# RF_PLL_channel.net
KiCad netlist of a schematic drawn in Altium Designer
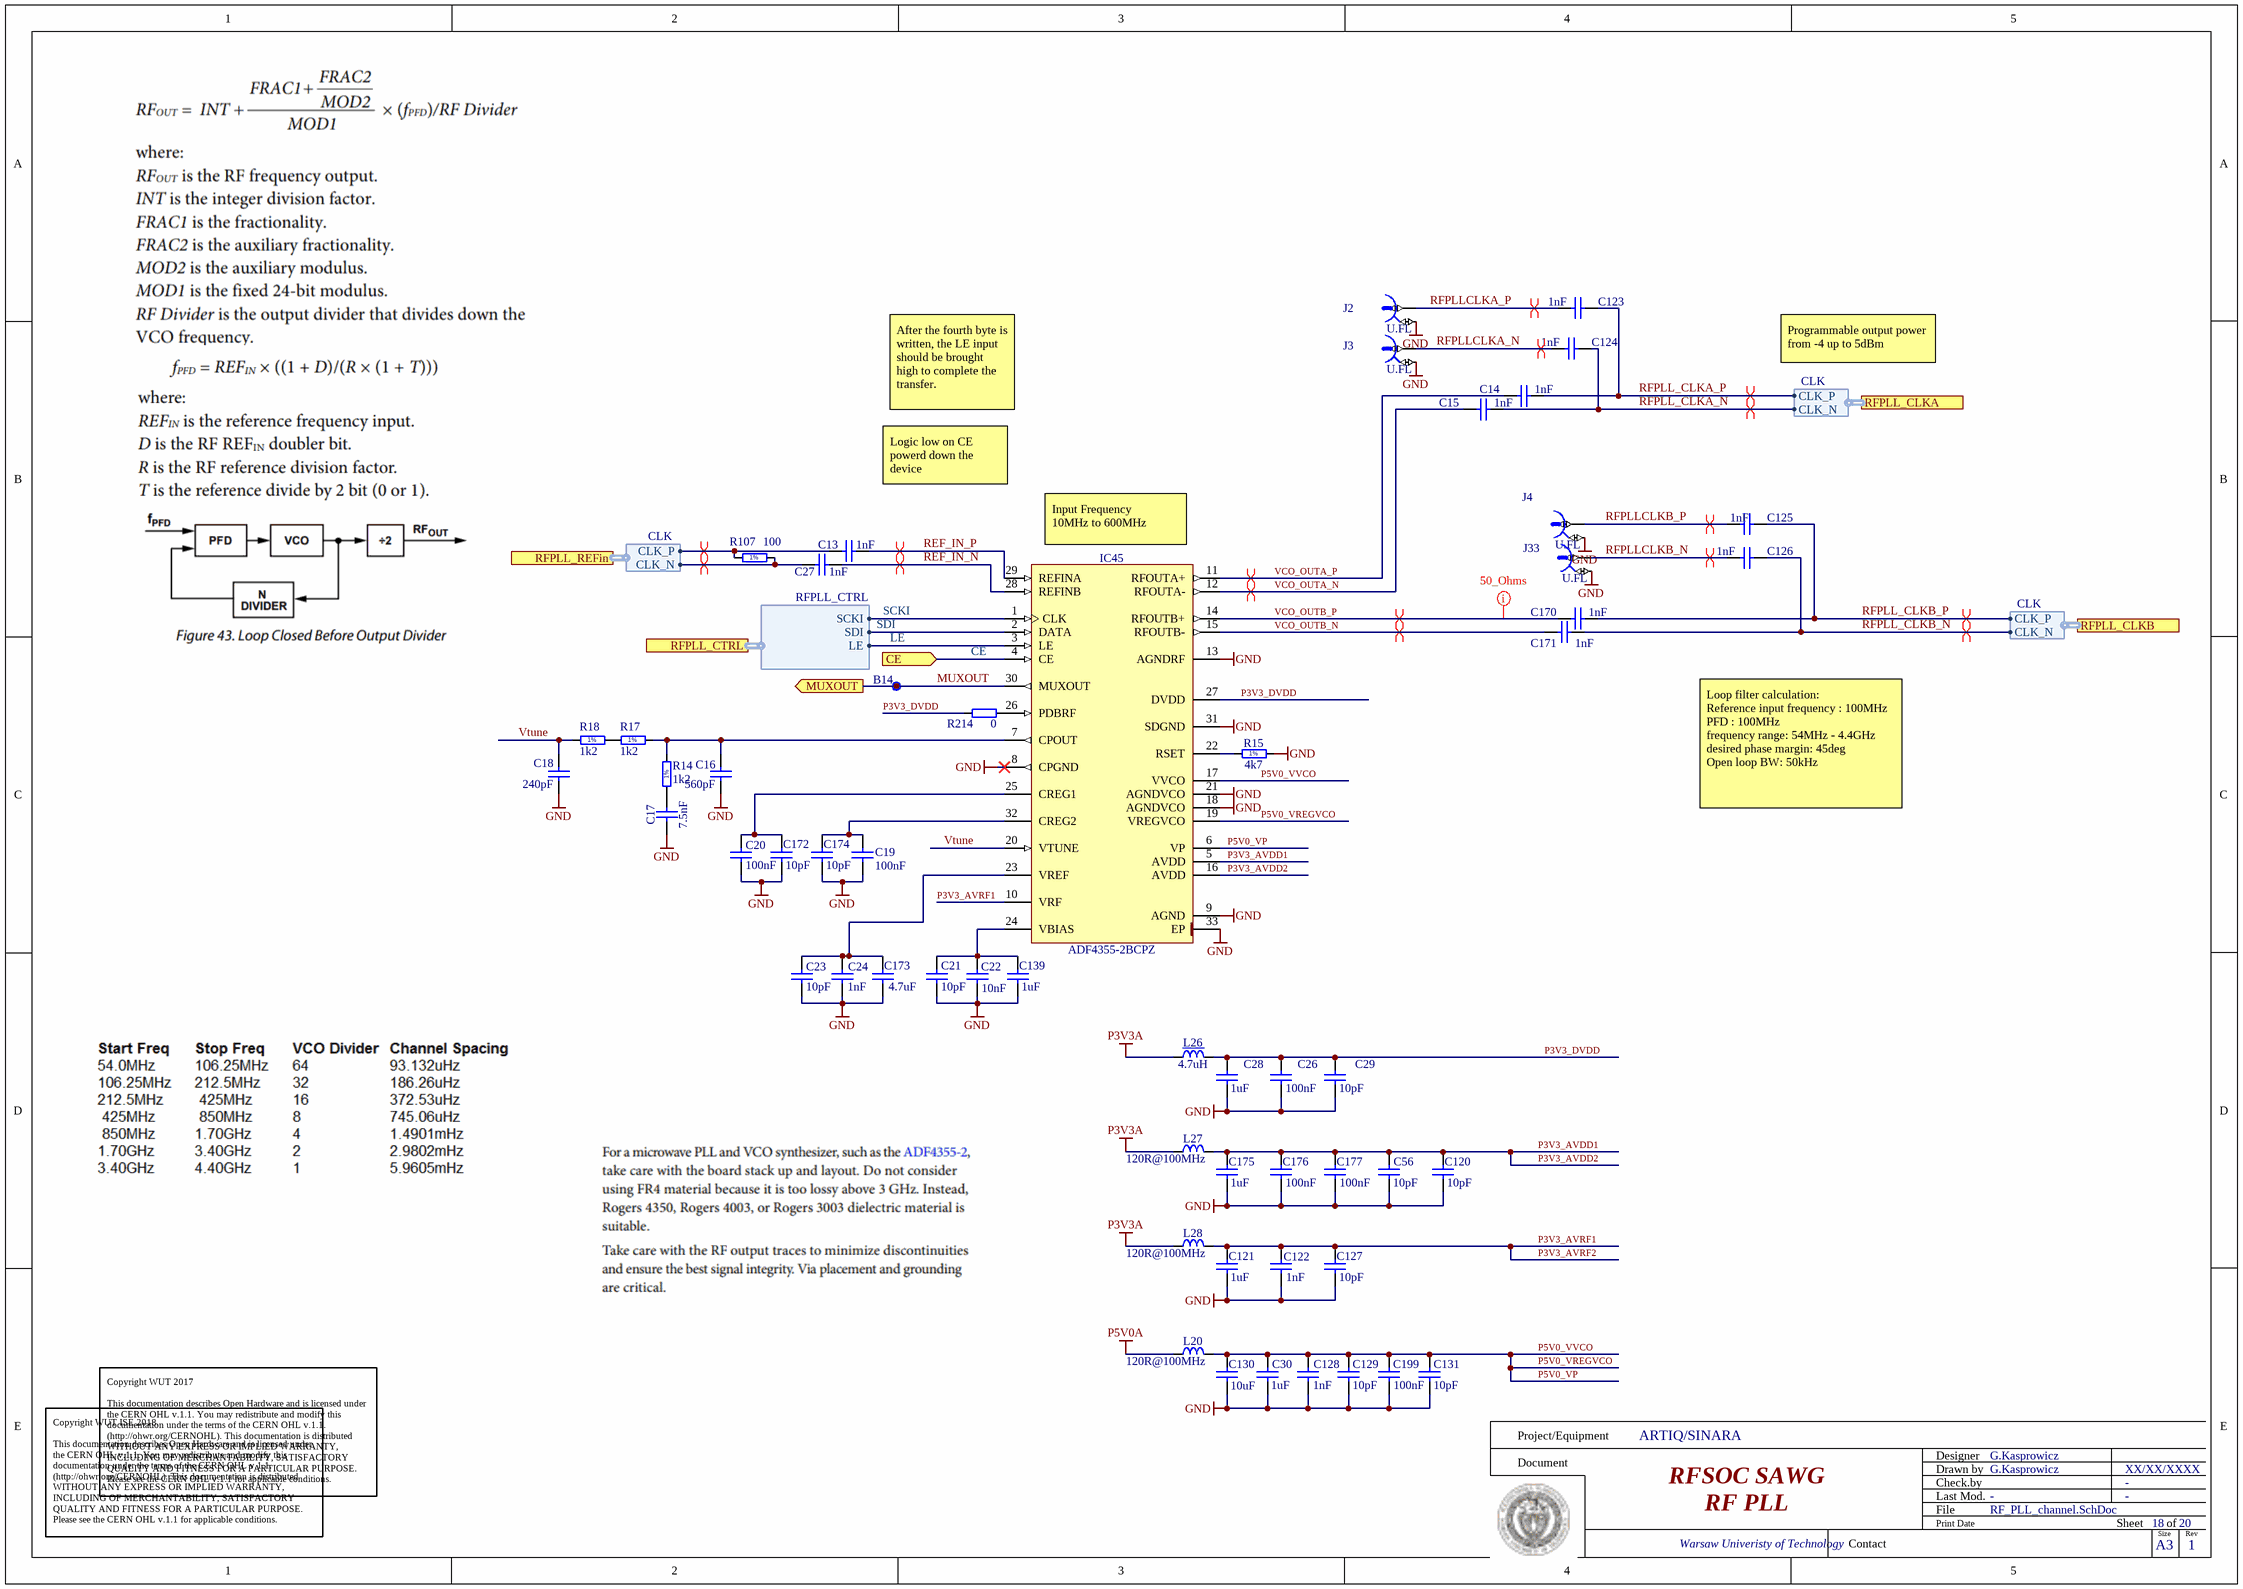
[diagram p0: RF_PLL_channel.SchDoc]

(export (version "E")
  (design (tool "Eeschema 10.0.6"))
  (components
    (comp (ref "B14")
      (value "SMD Pad")
      (footprint "C100")
      (description "Through Hole Pad")
      (fields (field (name "PART NUMBER") "SMD_PAD_D1MM") (field (name "AUTHOR") "CERN DEM JLC"))
      (libsource (lib "Eletro-mechanical") (part "Single SMD Pad (Round)"))
    )
    (comp (ref "C13")
      (value "1nF")
      (footprint "CAPC1005X55N")
      (description "Non-polarised capacitor")
      (fields
        (field (name "PART NUMBER") "CC0402_1NF_50V_10%_X7R")
        (field (name "VOLTAGE") "50V")
        (field (name "AUTHOR") "CERN DEM JLC")
      )
      (libsource (lib "Capacitors") (part "Capacitor - non polarized"))
    )
    (comp (ref "C14")
      (value "1nF")
      (footprint "CAPC1005X55N")
      (description "Non-polarised capacitor")
      (fields
        (field (name "PART NUMBER") "CC0402_1NF_50V_10%_X7R")
        (field (name "VOLTAGE") "50V")
        (field (name "AUTHOR") "CERN DEM JLC")
      )
      (libsource (lib "Capacitors") (part "Capacitor - non polarized"))
    )
    (comp (ref "C15")
      (value "1nF")
      (footprint "CAPC1005X55N")
      (description "Non-polarised capacitor")
      (fields
        (field (name "PART NUMBER") "CC0402_1NF_50V_10%_X7R")
        (field (name "VOLTAGE") "50V")
        (field (name "AUTHOR") "CERN DEM JLC")
      )
      (libsource (lib "Capacitors") (part "Capacitor - non polarized"))
    )
    (comp (ref "C16")
      (value "560pF")
      (footprint "CAPC1005X55N")
      (description "Non-polarised capacitor")
      (fields
        (field (name "PART NUMBER") "CC0402_560PF_50V_5%_C0G")
        (field (name "VOLTAGE") "50V")
        (field (name "AUTHOR") "CERN DEM JLC")
      )
      (libsource (lib "Capacitors") (part "Capacitor - non polarized"))
    )
    (comp (ref "C17")
      (value "7.5nF")
      (footprint "CAPC1608X87N")
      (description "Non-polarised capacitor")
      (fields
        (field (name "PART NUMBER") "CC0603_7.5NF_25V_5%_C0G")
        (field (name "VOLTAGE") "25V")
        (field (name "AUTHOR") "CERN DEM JLC")
      )
      (libsource (lib "Capacitors") (part "Capacitor - non polarized"))
    )
    (comp (ref "C18")
      (value "240pF")
      (footprint "CAPC1005X55N")
      (description "Non-polarised capacitor")
      (fields
        (field (name "PART NUMBER") "CC0402_240PF_50V_5%_C0G")
        (field (name "VOLTAGE") "50V")
        (field (name "AUTHOR") "CERN DEM JLC")
      )
      (libsource (lib "Capacitors") (part "Capacitor - non polarized"))
    )
    (comp (ref "C19")
      (value "100nF")
      (footprint "CAPC1005X55N")
      (description "Non-polarised capacitor")
      (fields
        (field (name "PART NUMBER") "CC0402_100NF_16V_10%_X5R")
        (field (name "VOLTAGE") "16V")
        (field (name "AUTHOR") "CERN DEM JLC")
      )
      (libsource (lib "Capacitors") (part "Capacitor - non polarized"))
    )
    (comp (ref "C20")
      (value "100nF")
      (footprint "CAPC1005X55N")
      (description "Non-polarised capacitor")
      (fields
        (field (name "PART NUMBER") "CC0402_100NF_16V_10%_X5R")
        (field (name "VOLTAGE") "16V")
        (field (name "AUTHOR") "CERN DEM JLC")
      )
      (libsource (lib "Capacitors") (part "Capacitor - non polarized"))
    )
    (comp (ref "C21")
      (value "10pF")
      (footprint "CAPC1005X55N")
      (description "Non-polarised capacitor")
      (fields
        (field (name "PART NUMBER") "CC0402_10PF_50V_5%_C0G")
        (field (name "VOLTAGE") "50V")
        (field (name "AUTHOR") "CERN DEM JLC")
      )
      (libsource (lib "Capacitors") (part "Capacitor - non polarized"))
    )
    (comp (ref "C22")
      (value "10nF")
      (footprint "CAPC1005X55N")
      (description "Non-polarised capacitor")
      (fields
        (field (name "PART NUMBER") "CC0402_10NF_16V_10%_X7R")
        (field (name "VOLTAGE") "16V")
        (field (name "AUTHOR") "CERN DEM JLC")
      )
      (libsource (lib "Capacitors") (part "Capacitor - non polarized"))
    )
    (comp (ref "C23")
      (value "10pF")
      (footprint "CAPC1005X55N")
      (description "Non-polarised capacitor")
      (fields
        (field (name "PART NUMBER") "CC0402_10PF_50V_5%_C0G")
        (field (name "VOLTAGE") "50V")
        (field (name "AUTHOR") "CERN DEM JLC")
      )
      (libsource (lib "Capacitors") (part "Capacitor - non polarized"))
    )
    (comp (ref "C24")
      (value "1nF")
      (footprint "CAPC1005X55N")
      (description "Non-polarised capacitor")
      (fields
        (field (name "PART NUMBER") "CC0402_1NF_50V_10%_X7R")
        (field (name "VOLTAGE") "50V")
        (field (name "AUTHOR") "CERN DEM JLC")
      )
      (libsource (lib "Capacitors") (part "Capacitor - non polarized"))
    )
    (comp (ref "C26")
      (value "100nF")
      (footprint "CAPC1005X55N")
      (description "Non-polarised capacitor")
      (fields
        (field (name "PART NUMBER") "CC0402_100NF_16V_10%_X5R")
        (field (name "VOLTAGE") "16V")
        (field (name "AUTHOR") "CERN DEM JLC")
      )
      (libsource (lib "Capacitors") (part "Capacitor - non polarized"))
    )
    (comp (ref "C27")
      (value "1nF")
      (footprint "CAPC1005X55N")
      (description "Non-polarised capacitor")
      (fields
        (field (name "PART NUMBER") "CC0402_1NF_50V_10%_X7R")
        (field (name "VOLTAGE") "50V")
        (field (name "AUTHOR") "CERN DEM JLC")
      )
      (libsource (lib "Capacitors") (part "Capacitor - non polarized"))
    )
    (comp (ref "C28")
      (value "1uF")
      (footprint "CAPC1005X55N")
      (description "Non-polarised capacitor")
      (fields
        (field (name "PART NUMBER") "CC0402_1UF_16V_10%_X5R")
        (field (name "VOLTAGE") "16V")
        (field (name "AUTHOR") "CERN DEM JLC")
      )
      (libsource (lib "Capacitors") (part "Capacitor - non polarized"))
    )
    (comp (ref "C29")
      (value "10pF")
      (footprint "CAPC1005X55N")
      (description "Non-polarised capacitor")
      (fields
        (field (name "PART NUMBER") "CC0402_10PF_50V_5%_C0G")
        (field (name "VOLTAGE") "50V")
        (field (name "AUTHOR") "CERN DEM JLC")
      )
      (libsource (lib "Capacitors") (part "Capacitor - non polarized"))
    )
    (comp (ref "C30")
      (value "1uF")
      (footprint "CAPC1005X55N")
      (description "Non-polarised capacitor")
      (fields
        (field (name "PART NUMBER") "CC0402_1UF_16V_10%_X5R")
        (field (name "VOLTAGE") "16V")
        (field (name "AUTHOR") "CERN DEM JLC")
      )
      (libsource (lib "Capacitors") (part "Capacitor - non polarized"))
    )
    (comp (ref "C56")
      (value "10pF")
      (footprint "CAPC1005X55N")
      (description "Non-polarised capacitor")
      (fields
        (field (name "PART NUMBER") "CC0402_10PF_50V_5%_C0G")
        (field (name "VOLTAGE") "50V")
        (field (name "AUTHOR") "CERN DEM JLC")
      )
      (libsource (lib "Capacitors") (part "Capacitor - non polarized"))
    )
    (comp (ref "C120")
      (value "10pF")
      (footprint "CAPC1005X55N")
      (description "Non-polarised capacitor")
      (fields
        (field (name "PART NUMBER") "CC0402_10PF_50V_5%_C0G")
        (field (name "VOLTAGE") "50V")
        (field (name "AUTHOR") "CERN DEM JLC")
      )
      (libsource (lib "Capacitors") (part "Capacitor - non polarized"))
    )
    (comp (ref "C121")
      (value "1uF")
      (footprint "CAPC1005X55N")
      (description "Non-polarised capacitor")
      (fields
        (field (name "PART NUMBER") "CC0402_1UF_16V_10%_X5R")
        (field (name "VOLTAGE") "16V")
        (field (name "AUTHOR") "CERN DEM JLC")
      )
      (libsource (lib "Capacitors") (part "Capacitor - non polarized"))
    )
    (comp (ref "C122")
      (value "1nF")
      (footprint "CAPC1005X55N")
      (description "Non-polarised capacitor")
      (fields
        (field (name "PART NUMBER") "CC0402_1NF_50V_10%_X7R")
        (field (name "VOLTAGE") "50V")
        (field (name "AUTHOR") "CERN DEM JLC")
      )
      (libsource (lib "Capacitors") (part "Capacitor - non polarized"))
    )
    (comp (ref "C123")
      (value "1nF")
      (footprint "CAPC1005X55N")
      (description "Non-polarised capacitor")
      (fields
        (field (name "PART NUMBER") "CC0402_1NF_50V_10%_X7R")
        (field (name "VOLTAGE") "50V")
        (field (name "AUTHOR") "CERN DEM JLC")
      )
      (libsource (lib "Capacitors") (part "Capacitor - non polarized"))
    )
    (comp (ref "C124")
      (value "1nF")
      (footprint "CAPC1005X55N")
      (description "Non-polarised capacitor")
      (fields
        (field (name "PART NUMBER") "CC0402_1NF_50V_10%_X7R")
        (field (name "VOLTAGE") "50V")
        (field (name "AUTHOR") "CERN DEM JLC")
      )
      (libsource (lib "Capacitors") (part "Capacitor - non polarized"))
    )
    (comp (ref "C125")
      (value "1nF")
      (footprint "CAPC1005X55N")
      (description "Non-polarised capacitor")
      (fields
        (field (name "PART NUMBER") "CC0402_1NF_50V_10%_X7R")
        (field (name "VOLTAGE") "50V")
        (field (name "AUTHOR") "CERN DEM JLC")
      )
      (libsource (lib "Capacitors") (part "Capacitor - non polarized"))
    )
    (comp (ref "C126")
      (value "1nF")
      (footprint "CAPC1005X55N")
      (description "Non-polarised capacitor")
      (fields
        (field (name "PART NUMBER") "CC0402_1NF_50V_10%_X7R")
        (field (name "VOLTAGE") "50V")
        (field (name "AUTHOR") "CERN DEM JLC")
      )
      (libsource (lib "Capacitors") (part "Capacitor - non polarized"))
    )
    (comp (ref "C127")
      (value "10pF")
      (footprint "CAPC1005X55N")
      (description "Non-polarised capacitor")
      (fields
        (field (name "PART NUMBER") "CC0402_10PF_50V_5%_C0G")
        (field (name "VOLTAGE") "50V")
        (field (name "AUTHOR") "CERN DEM JLC")
      )
      (libsource (lib "Capacitors") (part "Capacitor - non polarized"))
    )
    (comp (ref "C128")
      (value "1nF")
      (footprint "CAPC1005X55N")
      (description "Non-polarised capacitor")
      (fields
        (field (name "PART NUMBER") "CC0402_1NF_50V_10%_X7R")
        (field (name "VOLTAGE") "50V")
        (field (name "AUTHOR") "CERN DEM JLC")
      )
      (libsource (lib "Capacitors") (part "Capacitor - non polarized"))
    )
    (comp (ref "C129")
      (value "10pF")
      (footprint "CAPC1005X55N")
      (description "Non-polarised capacitor")
      (fields
        (field (name "PART NUMBER") "CC0402_10PF_50V_5%_C0G")
        (field (name "VOLTAGE") "50V")
        (field (name "AUTHOR") "CERN DEM JLC")
      )
      (libsource (lib "Capacitors") (part "Capacitor - non polarized"))
    )
    (comp (ref "C130")
      (value "10uF")
      (footprint "CAPC1608X80N")
      (description "Non-polarised capacitor")
      (fields
        (field (name "PART NUMBER") "CC0603_10UF_16V_20%_X5R")
        (field (name "VOLTAGE") "16V")
        (field (name "AUTHOR") "CERN DEM MR")
      )
      (libsource (lib "Capacitors") (part "Capacitor - non polarized"))
    )
    (comp (ref "C131")
      (value "10pF")
      (footprint "CAPC1005X55N")
      (description "Non-polarised capacitor")
      (fields
        (field (name "PART NUMBER") "CC0402_10PF_50V_5%_C0G")
        (field (name "VOLTAGE") "50V")
        (field (name "AUTHOR") "CERN DEM JLC")
      )
      (libsource (lib "Capacitors") (part "Capacitor - non polarized"))
    )
    (comp (ref "C139")
      (value "1uF")
      (footprint "CAPC1005X55N")
      (description "Non-polarised capacitor")
      (fields
        (field (name "PART NUMBER") "CC0402_1UF_16V_10%_X5R")
        (field (name "VOLTAGE") "16V")
        (field (name "AUTHOR") "CERN DEM JLC")
      )
      (libsource (lib "Capacitors") (part "Capacitor - non polarized"))
    )
    (comp (ref "C170")
      (value "1nF")
      (footprint "CAPC1005X55N")
      (description "Non-polarised capacitor")
      (fields
        (field (name "PART NUMBER") "CC0402_1NF_50V_10%_X7R")
        (field (name "VOLTAGE") "50V")
        (field (name "AUTHOR") "CERN DEM JLC")
      )
      (libsource (lib "Capacitors") (part "Capacitor - non polarized"))
    )
    (comp (ref "C171")
      (value "1nF")
      (footprint "CAPC1005X55N")
      (description "Non-polarised capacitor")
      (fields
        (field (name "PART NUMBER") "CC0402_1NF_50V_10%_X7R")
        (field (name "VOLTAGE") "50V")
        (field (name "AUTHOR") "CERN DEM JLC")
      )
      (libsource (lib "Capacitors") (part "Capacitor - non polarized"))
    )
    (comp (ref "C172")
      (value "10pF")
      (footprint "CAPC1005X55N")
      (description "Non-polarised capacitor")
      (fields
        (field (name "PART NUMBER") "CC0402_10PF_50V_5%_C0G")
        (field (name "VOLTAGE") "50V")
        (field (name "AUTHOR") "CERN DEM JLC")
      )
      (libsource (lib "Capacitors") (part "Capacitor - non polarized"))
    )
    (comp (ref "C173")
      (value "4.7uF")
      (footprint "CAPC1608X80N")
      (description "Non-polarised capacitor")
      (fields
        (field (name "PART NUMBER") "CC0603_4U7F_16V_10%_X5R")
        (field (name "VOLTAGE") "16V")
        (field (name "AUTHOR") "CERN DEM MR")
      )
      (libsource (lib "Capacitors") (part "Capacitor - non polarized"))
    )
    (comp (ref "C174")
      (value "10pF")
      (footprint "CAPC1005X55N")
      (description "Non-polarised capacitor")
      (fields
        (field (name "PART NUMBER") "CC0402_10PF_50V_5%_C0G")
        (field (name "VOLTAGE") "50V")
        (field (name "AUTHOR") "CERN DEM JLC")
      )
      (libsource (lib "Capacitors") (part "Capacitor - non polarized"))
    )
    (comp (ref "C175")
      (value "1uF")
      (footprint "CAPC1005X55N")
      (description "Non-polarised capacitor")
      (fields
        (field (name "PART NUMBER") "CC0402_1UF_16V_10%_X5R")
        (field (name "VOLTAGE") "16V")
        (field (name "AUTHOR") "CERN DEM JLC")
      )
      (libsource (lib "Capacitors") (part "Capacitor - non polarized"))
    )
    (comp (ref "C176")
      (value "100nF")
      (footprint "CAPC1005X55N")
      (description "Non-polarised capacitor")
      (fields
        (field (name "PART NUMBER") "CC0402_100NF_16V_10%_X5R")
        (field (name "VOLTAGE") "16V")
        (field (name "AUTHOR") "CERN DEM JLC")
      )
      (libsource (lib "Capacitors") (part "Capacitor - non polarized"))
    )
    (comp (ref "C177")
      (value "100nF")
      (footprint "CAPC1005X55N")
      (description "Non-polarised capacitor")
      (fields
        (field (name "PART NUMBER") "CC0402_100NF_16V_10%_X5R")
        (field (name "VOLTAGE") "16V")
        (field (name "AUTHOR") "CERN DEM JLC")
      )
      (libsource (lib "Capacitors") (part "Capacitor - non polarized"))
    )
    (comp (ref "C199")
      (value "100nF")
      (footprint "CAPC1005X55N")
      (description "Non-polarised capacitor")
      (fields
        (field (name "PART NUMBER") "CC0402_100NF_16V_10%_X5R")
        (field (name "VOLTAGE") "16V")
        (field (name "AUTHOR") "CERN DEM JLC")
      )
      (libsource (lib "Capacitors") (part "Capacitor - non polarized"))
    )
    (comp (ref "IC45")
      (value "ADF4355-2BCPZ")
      (footprint "QFN50P500X500X80-33N-S375")
      (description "Microwave Wideband Synthesizer with Integrated VCO")
      (fields
        (field (name "MANUFACTURER") "ANALOG DEVICES")
        (field (name "MANUFACTURER PART NUMBER") "ADF4355-2BCP")
        (field (name "AUTHOR") "CERN DEM BC")
      )
      (libsource (lib "ICs And Semiconductors") (part "ADF4355-2"))
    )
    (comp (ref "J2")
      (value "U.FL")
      (footprint "HIROSE_U.FL-R-SMT-1(10)")
      (fields
        (field (name "PART NUMBER") "HIROSE_U.FL-R-SMT-1(10)")
        (field (name "MANUFACTURER") "HIROSE (HRS)")
        (field (name "MANUFACTURER PART NUMBER") "U.FL-R-SMT-1(10)")
        (field (name "AUTHOR") "CERN DEM JLC")
      )
      (libsource (lib "Connectors") (part "Coax_1Male_1Shield"))
    )
    (comp (ref "J3")
      (value "U.FL")
      (footprint "HIROSE_U.FL-R-SMT-1(10)")
      (fields
        (field (name "PART NUMBER") "HIROSE_U.FL-R-SMT-1(10)")
        (field (name "MANUFACTURER") "HIROSE (HRS)")
        (field (name "MANUFACTURER PART NUMBER") "U.FL-R-SMT-1(10)")
        (field (name "AUTHOR") "CERN DEM JLC")
      )
      (libsource (lib "Connectors") (part "Coax_1Male_1Shield"))
    )
    (comp (ref "J4")
      (value "U.FL")
      (footprint "HIROSE_U.FL-R-SMT-1(10)")
      (fields
        (field (name "PART NUMBER") "HIROSE_U.FL-R-SMT-1(10)")
        (field (name "MANUFACTURER") "HIROSE (HRS)")
        (field (name "MANUFACTURER PART NUMBER") "U.FL-R-SMT-1(10)")
        (field (name "AUTHOR") "CERN DEM JLC")
      )
      (libsource (lib "Connectors") (part "Coax_1Male_1Shield"))
    )
    (comp (ref "J33")
      (value "U.FL")
      (footprint "HIROSE_U.FL-R-SMT-1(10)")
      (fields
        (field (name "PART NUMBER") "HIROSE_U.FL-R-SMT-1(10)")
        (field (name "MANUFACTURER") "HIROSE (HRS)")
        (field (name "MANUFACTURER PART NUMBER") "U.FL-R-SMT-1(10)")
        (field (name "AUTHOR") "CERN DEM JLC")
      )
      (libsource (lib "Connectors") (part "Coax_1Male_1Shield"))
    )
    (comp (ref "L20")
      (value "120R@100MHz")
      (footprint "INDC1608X95N")
      (description "Inductor")
      (fields
        (field (name "PART NUMBER") "IND0603_MURATA_BLM18PG121SN1D")
        (field (name "POWER") "2A")
        (field (name "AUTHOR") "CERN DEM BC")
      )
      (libsource (lib "Inductors & Transformers") (part "Inductor"))
    )
    (comp (ref "L26")
      (value "4.7uH")
      (footprint "INDC2012X145N")
      (description "Inductor With Core")
      (fields
        (field (name "PART NUMBER") "IND0805_4.7UH_20%_KEMET_L-DWI")
        (field (name "POWER") "360mA")
        (field (name "AUTHOR") "CERN DEM JLC")
      )
      (libsource (lib "Inductors & Transformers") (part "Inductor With Magnetic core"))
    )
    (comp (ref "L27")
      (value "120R@100MHz")
      (footprint "INDC1608X95N")
      (description "Inductor")
      (fields
        (field (name "PART NUMBER") "IND0603_MURATA_BLM18PG121SN1D")
        (field (name "POWER") "2A")
        (field (name "AUTHOR") "CERN DEM BC")
      )
      (libsource (lib "Inductors & Transformers") (part "Inductor"))
    )
    (comp (ref "L28")
      (value "120R@100MHz")
      (footprint "INDC1608X95N")
      (description "Inductor")
      (fields
        (field (name "PART NUMBER") "IND0603_MURATA_BLM18PG121SN1D")
        (field (name "POWER") "2A")
        (field (name "AUTHOR") "CERN DEM BC")
      )
      (libsource (lib "Inductors & Transformers") (part "Inductor"))
    )
    (comp (ref "R14")
      (value "1k2")
      (footprint "RESC1005X40N")
      (description "Resistor - 1%")
      (fields
        (field (name "PART NUMBER") "R0402_1K2_1%_0.0625W_100PPM")
        (field (name "POWER") "0.0625W")
        (field (name "AUTHOR") "CERN DEM JLC")
      )
      (libsource (lib "Resistors") (part "Resistor - 1%"))
    )
    (comp (ref "R15")
      (value "4k7")
      (footprint "RESC1005X40N")
      (description "Resistor - 1%")
      (fields
        (field (name "PART NUMBER") "R0402_4K7_1%_0.0625W_100PPM")
        (field (name "POWER") "0.0625W")
        (field (name "AUTHOR") "CERN DEM JLC")
      )
      (libsource (lib "Resistors") (part "Resistor - 1%"))
    )
    (comp (ref "R17")
      (value "1k2")
      (footprint "RESC1005X40N")
      (description "Resistor - 1%")
      (fields
        (field (name "PART NUMBER") "R0402_1K2_1%_0.0625W_100PPM")
        (field (name "POWER") "0.0625W")
        (field (name "AUTHOR") "CERN DEM JLC")
      )
      (libsource (lib "Resistors") (part "Resistor - 1%"))
    )
    (comp (ref "R18")
      (value "1k2")
      (footprint "RESC1005X40N")
      (description "Resistor - 1%")
      (fields
        (field (name "PART NUMBER") "R0402_1K2_1%_0.0625W_100PPM")
        (field (name "POWER") "0.0625W")
        (field (name "AUTHOR") "CERN DEM JLC")
      )
      (libsource (lib "Resistors") (part "Resistor - 1%"))
    )
    (comp (ref "R107")
      (value "100")
      (footprint "RESC1005X40N")
      (description "Resistor - 1%")
      (fields
        (field (name "PART NUMBER") "R0402_100R_1%_0.0625W_100PPM")
        (field (name "POWER") "0.0625W")
        (field (name "AUTHOR") "CERN DEM JLC")
      )
      (libsource (lib "Resistors") (part "Resistor - 1%"))
    )
    (comp (ref "R214")
      (value "0")
      (footprint "RESC1005X40N")
      (description "Resistor")
      (fields
        (field (name "PART NUMBER") "R0402_0R_JUMPER")
        (field (name "MANUFACTURER") "GENERIC")
        (field (name "AUTHOR") "CERN DEM JLC")
      )
      (libsource (lib "Resistors") (part "Resistor"))
    )
  )
  (nets
    (net (code "3") (name "/CE") (class "Default")
      (node (ref "IC45") (pin "4") (pinfunction "CE_4") (pintype "input"))
    )
    (net (code "4") (name "/LE") (class "Default")
      (node (ref "IC45") (pin "3") (pinfunction "LE_3") (pintype "input"))
    )
    (net (code "5") (name "/MUXOUT") (class "Default")
      (node (ref "B14") (pin "1") (pinfunction "1_1") (pintype "bidirectional"))
      (node (ref "IC45") (pin "30") (pinfunction "MUXOUT_30") (pintype "output"))
    )
    (net (code "6") (name "/P3V3_AVDD1") (class "Default")
      (node (ref "C120") (pin "2") (pinfunction "2_2") (pintype "passive"))
      (node (ref "C175") (pin "2") (pinfunction "2_2") (pintype "passive"))
      (node (ref "C176") (pin "2") (pinfunction "2_2") (pintype "passive"))
      (node (ref "C177") (pin "2") (pinfunction "2_2") (pintype "passive"))
      (node (ref "C56") (pin "2") (pinfunction "2_2") (pintype "passive"))
      (node (ref "IC45") (pin "16") (pinfunction "AVDD_16") (pintype "power_in"))
      (node (ref "IC45") (pin "5") (pinfunction "AVDD_5") (pintype "power_in"))
      (node (ref "L27") (pin "1") (pinfunction "1_1") (pintype "passive"))
    )
    (net (code "7") (name "/P3V3_AVRF1") (class "Default")
      (node (ref "C121") (pin "2") (pinfunction "2_2") (pintype "passive"))
      (node (ref "C122") (pin "2") (pinfunction "2_2") (pintype "passive"))
      (node (ref "C127") (pin "2") (pinfunction "2_2") (pintype "passive"))
      (node (ref "IC45") (pin "10") (pinfunction "VRF_10") (pintype "passive"))
      (node (ref "L28") (pin "1") (pinfunction "1_1") (pintype "passive"))
    )
    (net (code "8") (name "/P3V3_DVDD") (class "Default")
      (node (ref "C26") (pin "2") (pinfunction "2_2") (pintype "passive"))
      (node (ref "C28") (pin "2") (pinfunction "2_2") (pintype "passive"))
      (node (ref "C29") (pin "2") (pinfunction "2_2") (pintype "passive"))
      (node (ref "IC45") (pin "27") (pinfunction "DVDD_27") (pintype "power_in"))
      (node (ref "L26") (pin "2") (pinfunction "2_2") (pintype "passive"))
      (node (ref "R214") (pin "1") (pinfunction "1_1") (pintype "passive"))
    )
    (net (code "9") (name "/P5V0_VP") (class "Default")
      (node (ref "C128") (pin "2") (pinfunction "2_2") (pintype "passive"))
      (node (ref "C129") (pin "2") (pinfunction "2_2") (pintype "passive"))
      (node (ref "C130") (pin "2") (pinfunction "2_2") (pintype "passive"))
      (node (ref "C131") (pin "2") (pinfunction "2_2") (pintype "passive"))
      (node (ref "C199") (pin "2") (pinfunction "2_2") (pintype "passive"))
      (node (ref "C30") (pin "2") (pinfunction "2_2") (pintype "passive"))
      (node (ref "IC45") (pin "17") (pinfunction "VVCO_17") (pintype "power_in"))
      (node (ref "IC45") (pin "19") (pinfunction "VREGVCO_19") (pintype "power_in"))
      (node (ref "IC45") (pin "6") (pinfunction "VP_6") (pintype "power_in"))
      (node (ref "L20") (pin "1") (pinfunction "1_1") (pintype "passive"))
    )
    (net (code "10") (name "/REF_IN_N") (class "Default")
      (node (ref "C27") (pin "2") (pinfunction "2_2") (pintype "passive"))
      (node (ref "IC45") (pin "28") (pinfunction "REFINB_28") (pintype "input"))
    )
    (net (code "11") (name "/REF_IN_P") (class "Default")
      (node (ref "C13") (pin "2") (pinfunction "2_2") (pintype "passive"))
      (node (ref "IC45") (pin "29") (pinfunction "REFINA_29") (pintype "input"))
    )
    (net (code "12") (name "/RFPLLCLKA_N") (class "Default")
      (node (ref "C124") (pin "2") (pinfunction "2_2") (pintype "passive"))
      (node (ref "J3") (pin "1") (pinfunction "1_1") (pintype "bidirectional"))
    )
    (net (code "13") (name "/RFPLLCLKA_P") (class "Default")
      (node (ref "C123") (pin "2") (pinfunction "2_2") (pintype "passive"))
      (node (ref "J2") (pin "1") (pinfunction "1_1") (pintype "bidirectional"))
    )
    (net (code "14") (name "/RFPLLCLKB_N") (class "Default")
      (node (ref "C126") (pin "2") (pinfunction "2_2") (pintype "passive"))
      (node (ref "J33") (pin "1") (pinfunction "1_1") (pintype "bidirectional"))
    )
    (net (code "15") (name "/RFPLLCLKB_P") (class "Default")
      (node (ref "C125") (pin "2") (pinfunction "2_2") (pintype "passive"))
      (node (ref "J4") (pin "1") (pinfunction "1_1") (pintype "bidirectional"))
    )
    (net (code "16") (name "/RFPLL_CLKA_N") (class "Default")
      (node (ref "C124") (pin "1") (pinfunction "1_1") (pintype "passive"))
      (node (ref "C15") (pin "2") (pinfunction "2_2") (pintype "passive"))
    )
    (net (code "17") (name "/RFPLL_CLKA_P") (class "Default")
      (node (ref "C123") (pin "1") (pinfunction "1_1") (pintype "passive"))
      (node (ref "C14") (pin "2") (pinfunction "2_2") (pintype "passive"))
    )
    (net (code "18") (name "/RFPLL_CLKB_N") (class "Default")
      (node (ref "C126") (pin "1") (pinfunction "1_1") (pintype "passive"))
      (node (ref "C171") (pin "2") (pinfunction "2_2") (pintype "passive"))
    )
    (net (code "19") (name "/RFPLL_CLKB_P") (class "Default")
      (node (ref "C125") (pin "1") (pinfunction "1_1") (pintype "passive"))
      (node (ref "C170") (pin "2") (pinfunction "2_2") (pintype "passive"))
    )
    (net (code "20") (name "/SCKI") (class "Default")
      (node (ref "IC45") (pin "1") (pinfunction "CLK_1") (pintype "input"))
    )
    (net (code "21") (name "/SDI") (class "Default")
      (node (ref "IC45") (pin "2") (pinfunction "DATA_2") (pintype "input"))
    )
    (net (code "22") (name "/VCO_OUTA_N") (class "Default")
      (node (ref "C15") (pin "1") (pinfunction "1_1") (pintype "passive"))
      (node (ref "IC45") (pin "12") (pinfunction "RFOUTA-_12") (pintype "output"))
    )
    (net (code "23") (name "/VCO_OUTA_P") (class "Default")
      (node (ref "C14") (pin "1") (pinfunction "1_1") (pintype "passive"))
      (node (ref "IC45") (pin "11") (pinfunction "RFOUTA+_11") (pintype "output"))
    )
    (net (code "24") (name "/VCO_OUTB_N") (class "Default")
      (node (ref "C171") (pin "1") (pinfunction "1_1") (pintype "passive"))
      (node (ref "IC45") (pin "15") (pinfunction "RFOUTB-_15") (pintype "output"))
    )
    (net (code "25") (name "/VCO_OUTB_P") (class "Default")
      (node (ref "C170") (pin "1") (pinfunction "1_1") (pintype "passive"))
      (node (ref "IC45") (pin "14") (pinfunction "RFOUTB+_14") (pintype "output"))
    )
    (net (code "26") (name "/Vtune") (class "Default")
      (node (ref "C18") (pin "2") (pinfunction "2_2") (pintype "passive"))
      (node (ref "IC45") (pin "20") (pinfunction "VTUNE_20") (pintype "input"))
      (node (ref "R18") (pin "2") (pinfunction "2_2") (pintype "passive"))
    )
    (net (code "29") (name "GND") (class "Default")
      (node (ref "C120") (pin "1") (pinfunction "1_1") (pintype "passive"))
      (node (ref "C121") (pin "1") (pinfunction "1_1") (pintype "passive"))
      (node (ref "C122") (pin "1") (pinfunction "1_1") (pintype "passive"))
      (node (ref "C127") (pin "1") (pinfunction "1_1") (pintype "passive"))
      (node (ref "C128") (pin "1") (pinfunction "1_1") (pintype "passive"))
      (node (ref "C129") (pin "1") (pinfunction "1_1") (pintype "passive"))
      (node (ref "C130") (pin "1") (pinfunction "1_1") (pintype "passive"))
      (node (ref "C131") (pin "1") (pinfunction "1_1") (pintype "passive"))
      (node (ref "C139") (pin "1") (pinfunction "1_1") (pintype "passive"))
      (node (ref "C16") (pin "1") (pinfunction "1_1") (pintype "passive"))
      (node (ref "C17") (pin "1") (pinfunction "1_1") (pintype "passive"))
      (node (ref "C172") (pin "1") (pinfunction "1_1") (pintype "passive"))
      (node (ref "C173") (pin "1") (pinfunction "1_1") (pintype "passive"))
      (node (ref "C174") (pin "1") (pinfunction "1_1") (pintype "passive"))
      (node (ref "C175") (pin "1") (pinfunction "1_1") (pintype "passive"))
      (node (ref "C176") (pin "1") (pinfunction "1_1") (pintype "passive"))
      (node (ref "C177") (pin "1") (pinfunction "1_1") (pintype "passive"))
      (node (ref "C18") (pin "1") (pinfunction "1_1") (pintype "passive"))
      (node (ref "C19") (pin "1") (pinfunction "1_1") (pintype "passive"))
      (node (ref "C199") (pin "1") (pinfunction "1_1") (pintype "passive"))
      (node (ref "C20") (pin "1") (pinfunction "1_1") (pintype "passive"))
      (node (ref "C21") (pin "1") (pinfunction "1_1") (pintype "passive"))
      (node (ref "C22") (pin "1") (pinfunction "1_1") (pintype "passive"))
      (node (ref "C23") (pin "1") (pinfunction "1_1") (pintype "passive"))
      (node (ref "C24") (pin "1") (pinfunction "1_1") (pintype "passive"))
      (node (ref "C26") (pin "1") (pinfunction "1_1") (pintype "passive"))
      (node (ref "C28") (pin "1") (pinfunction "1_1") (pintype "passive"))
      (node (ref "C29") (pin "1") (pinfunction "1_1") (pintype "passive"))
      (node (ref "C30") (pin "1") (pinfunction "1_1") (pintype "passive"))
      (node (ref "C56") (pin "1") (pinfunction "1_1") (pintype "passive"))
      (node (ref "IC45") (pin "13") (pinfunction "AGNDRF_13") (pintype "power_in"))
      (node (ref "IC45") (pin "18") (pinfunction "AGNDVCO_18") (pintype "power_in"))
      (node (ref "IC45") (pin "21") (pinfunction "AGNDVCO_21") (pintype "power_in"))
      (node (ref "IC45") (pin "31") (pinfunction "SDGND_31") (pintype "power_in"))
      (node (ref "IC45") (pin "33") (pinfunction "EP_33") (pintype "power_in"))
      (node (ref "IC45") (pin "8") (pinfunction "CPGND_8") (pintype "output"))
      (node (ref "IC45") (pin "9") (pinfunction "AGND_9") (pintype "power_in"))
      (node (ref "J2") (pin "2") (pinfunction "2_2") (pintype "bidirectional"))
      (node (ref "J3") (pin "2") (pinfunction "2_2") (pintype "bidirectional"))
      (node (ref "J33") (pin "2") (pinfunction "2_2") (pintype "bidirectional"))
      (node (ref "J4") (pin "2") (pinfunction "2_2") (pintype "bidirectional"))
      (node (ref "R15") (pin "2") (pinfunction "2_2") (pintype "passive"))
    )
    (net (code "30") (name "Net-(C13-Pad1)") (class "Default")
      (node (ref "C13") (pin "1") (pinfunction "1_1") (pintype "passive"))
      (node (ref "R107") (pin "1") (pinfunction "1_1") (pintype "passive"))
    )
    (net (code "31") (name "Net-(C17-Pad2)") (class "Default")
      (node (ref "C17") (pin "2") (pinfunction "2_2") (pintype "passive"))
      (node (ref "R14") (pin "1") (pinfunction "1_1") (pintype "passive"))
    )
    (net (code "32") (name "Net-(C27-Pad1)") (class "Default")
      (node (ref "C27") (pin "1") (pinfunction "1_1") (pintype "passive"))
      (node (ref "R107") (pin "2") (pinfunction "2_2") (pintype "passive"))
    )
    (net (code "33") (name "Net-(IC45-CPOUT)") (class "Default")
      (node (ref "C16") (pin "2") (pinfunction "2_2") (pintype "passive"))
      (node (ref "IC45") (pin "7") (pinfunction "CPOUT_7") (pintype "output"))
      (node (ref "R14") (pin "2") (pinfunction "2_2") (pintype "passive"))
      (node (ref "R17") (pin "1") (pinfunction "1_1") (pintype "passive"))
    )
    (net (code "34") (name "Net-(IC45-CREG1)") (class "Default")
      (node (ref "C172") (pin "2") (pinfunction "2_2") (pintype "passive"))
      (node (ref "C20") (pin "2") (pinfunction "2_2") (pintype "passive"))
      (node (ref "IC45") (pin "25") (pinfunction "CREG1_25") (pintype "power_in"))
    )
    (net (code "35") (name "Net-(IC45-CREG2)") (class "Default")
      (node (ref "C174") (pin "2") (pinfunction "2_2") (pintype "passive"))
      (node (ref "C19") (pin "2") (pinfunction "2_2") (pintype "passive"))
      (node (ref "IC45") (pin "32") (pinfunction "CREG2_32") (pintype "power_in"))
    )
    (net (code "36") (name "Net-(IC45-PDBRF)") (class "Default")
      (node (ref "IC45") (pin "26") (pinfunction "PDBRF_26") (pintype "input"))
      (node (ref "R214") (pin "2") (pinfunction "2_2") (pintype "passive"))
    )
    (net (code "37") (name "Net-(IC45-RSET)") (class "Default")
      (node (ref "IC45") (pin "22") (pinfunction "RSET_22") (pintype "passive"))
      (node (ref "R15") (pin "1") (pinfunction "1_1") (pintype "passive"))
    )
    (net (code "38") (name "Net-(IC45-VBIAS)") (class "Default")
      (node (ref "C139") (pin "2") (pinfunction "2_2") (pintype "passive"))
      (node (ref "C21") (pin "2") (pinfunction "2_2") (pintype "passive"))
      (node (ref "C22") (pin "2") (pinfunction "2_2") (pintype "passive"))
      (node (ref "IC45") (pin "24") (pinfunction "VBIAS_24") (pintype "power_in"))
    )
    (net (code "39") (name "Net-(IC45-VREF)") (class "Default")
      (node (ref "C173") (pin "2") (pinfunction "2_2") (pintype "passive"))
      (node (ref "C23") (pin "2") (pinfunction "2_2") (pintype "passive"))
      (node (ref "C24") (pin "2") (pinfunction "2_2") (pintype "passive"))
      (node (ref "IC45") (pin "23") (pinfunction "VREF_23") (pintype "passive"))
    )
    (net (code "40") (name "Net-(R17-Pad2)") (class "Default")
      (node (ref "R17") (pin "2") (pinfunction "2_2") (pintype "passive"))
      (node (ref "R18") (pin "1") (pinfunction "1_1") (pintype "passive"))
    )
    (net (code "41") (name "P3V3A") (class "Default")
      (node (ref "L26") (pin "1") (pinfunction "1_1") (pintype "passive"))
      (node (ref "L27") (pin "2") (pinfunction "2_2") (pintype "passive"))
      (node (ref "L28") (pin "2") (pinfunction "2_2") (pintype "passive"))
    )
    (net (code "42") (name "P5V0A") (class "Default")
      (node (ref "L20") (pin "2") (pinfunction "2_2") (pintype "passive"))
    )
  )
)
